# charger.net
KiCad netlist of a schematic drawn in Altium Designer
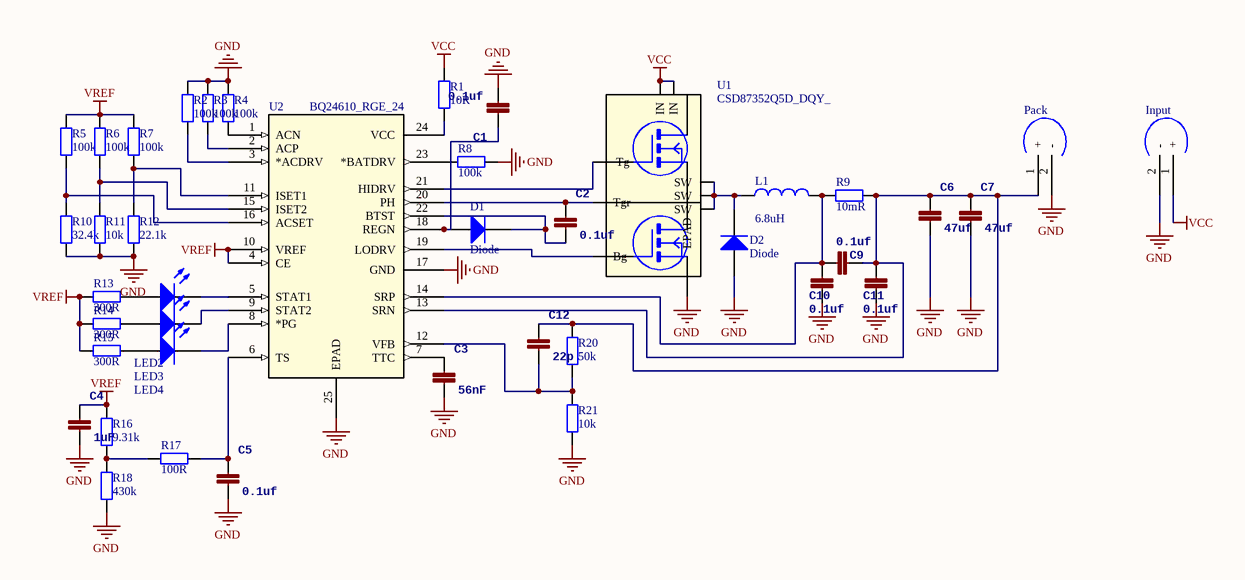
[diagram p0: charger.SchDoc]

(export (version "E")
  (design (tool "Eeschema 10.0.6"))
  (components
    (comp (ref "C1")
      (value "0.1uf")
      (footprint "0603")
      (description "电容")
      (fields (field (name "PARTNO") "CC0402ZRY5V7BB104"))
      (libsource (lib "") (part "CAP0402-CAP_2"))
    )
    (comp (ref "C2")
      (value "0.1uf")
      (footprint "0603")
      (description "电容")
      (fields (field (name "PARTNO") "CC0402ZRY5V7BB104"))
      (libsource (lib "") (part "CAP0402-CAP_1"))
    )
    (comp (ref "C3")
      (value "56nF")
      (footprint "0603")
      (description "电容")
      (fields (field (name "PARTNO") "CC0402ZRY5V7BB104"))
      (libsource (lib "") (part "CAP0402-CAP_1"))
    )
    (comp (ref "C4")
      (value "1uF")
      (footprint "0603")
      (description "电容")
      (fields (field (name "PARTNO") "CC0402ZRY5V7BB104"))
      (libsource (lib "") (part "CAP0402-CAP_1"))
    )
    (comp (ref "C5")
      (value "0.1uf")
      (footprint "0603")
      (description "电容")
      (fields (field (name "PARTNO") "CC0402ZRY5V7BB104"))
      (libsource (lib "") (part "CAP0402-CAP_1"))
    )
    (comp (ref "C6")
      (value "47uf")
      (footprint "1210")
      (description "电容")
      (fields (field (name "PARTNO") "CC0402ZRY5V7BB104"))
      (libsource (lib "") (part "CAP0402-CAP_1"))
    )
    (comp (ref "C7")
      (value "47uf")
      (footprint "1210")
      (description "电容")
      (fields (field (name "PARTNO") "CC0402ZRY5V7BB104"))
      (libsource (lib "") (part "CAP0402-CAP_1"))
    )
    (comp (ref "C9")
      (value "0.1uf")
      (footprint "0603")
      (description "电容")
      (fields (field (name "PARTNO") "CC0402ZRY5V7BB104"))
      (libsource (lib "mcu_board") (part "CAP0402-CAP"))
    )
    (comp (ref "C10")
      (value "0.1uf")
      (footprint "0603")
      (description "电容")
      (fields (field (name "PARTNO") "CC0402ZRY5V7BB104"))
      (libsource (lib "") (part "CAP0402-CAP_2"))
    )
    (comp (ref "C11")
      (value "0.1uf")
      (footprint "0603")
      (description "电容")
      (fields (field (name "PARTNO") "CC0402ZRY5V7BB104"))
      (libsource (lib "") (part "CAP0402-CAP_1"))
    )
    (comp (ref "C12")
      (value "22p")
      (footprint "0603")
      (description "电容")
      (fields (field (name "PARTNO") "CC0402ZRY5V7BB104"))
      (libsource (lib "") (part "CAP0402-CAP_1"))
    )
    (comp (ref "D1")
      (value "Diode")
      (footprint "0805")
      (description "Default Diode")
      (fields (field (name "PUBLISHER") "Altium Limited"))
      (libsource (lib "Miscellaneous Devices") (part "Diode"))
    )
    (comp (ref "D2")
      (value "Diode")
      (footprint "SMC")
      (description "Default Diode")
      (fields (field (name "PUBLISHER") "Altium Limited"))
      (libsource (lib "Miscellaneous Devices") (part "Diode"))
    )
    (comp (ref "Input")
      (value "Battery_AWG12")
      (footprint "Battery_AWG12")
      (libsource (lib "sch") (part "Battery_AWG12"))
    )
    (comp (ref "L1")
      (value "6.8uH")
      (footprint "GDRH127")
      (description "Inductor")
      (fields (field (name "PUBLISHER") "Altium Limited"))
      (libsource (lib "Miscellaneous Devices") (part "Inductor"))
    )
    (comp (ref "LED2")
      (value "LED0")
      (footprint "0603")
      (description "Typical INFRARED GaAs LED")
      (fields (field (name "PUBLISHER") "Altium Limited"))
      (libsource (lib "Miscellaneous Devices") (part "LED0"))
    )
    (comp (ref "LED3")
      (value "LED0")
      (footprint "0603")
      (description "Typical INFRARED GaAs LED")
      (fields (field (name "PUBLISHER") "Altium Limited"))
      (libsource (lib "Miscellaneous Devices") (part "LED0"))
    )
    (comp (ref "LED4")
      (value "LED0")
      (footprint "0603")
      (description "Typical INFRARED GaAs LED")
      (fields (field (name "PUBLISHER") "Altium Limited"))
      (libsource (lib "Miscellaneous Devices") (part "LED0"))
    )
    (comp (ref "Pack")
      (value "Battery_AWG12")
      (footprint "Battery_AWG12")
      (libsource (lib "") (part "Battery_AWG12_1"))
    )
    (comp (ref "R1")
      (value "10R")
      (footprint "0603")
      (description "电阻")
      (fields (field (name "PUBLISHER") "Altium Limited"))
      (libsource (lib "") (part "Res2_2"))
    )
    (comp (ref "R2")
      (value "100k")
      (footprint "0603")
      (description "电阻")
      (fields (field (name "PUBLISHER") "Altium Limited"))
      (libsource (lib "") (part "Res2_2"))
    )
    (comp (ref "R3")
      (value "100k")
      (footprint "0603")
      (description "电阻")
      (fields (field (name "PUBLISHER") "Altium Limited"))
      (libsource (lib "") (part "Res2_2"))
    )
    (comp (ref "R4")
      (value "100k")
      (footprint "0603")
      (description "电阻")
      (fields (field (name "PUBLISHER") "Altium Limited"))
      (libsource (lib "mcu_board") (part "Res2"))
    )
    (comp (ref "R5")
      (value "100k")
      (footprint "0603")
      (description "电阻")
      (fields (field (name "PUBLISHER") "Altium Limited"))
      (libsource (lib "") (part "Res2_2"))
    )
    (comp (ref "R6")
      (value "100k")
      (footprint "0603")
      (description "电阻")
      (fields (field (name "PUBLISHER") "Altium Limited"))
      (libsource (lib "") (part "Res2_2"))
    )
    (comp (ref "R7")
      (value "100k")
      (footprint "0603")
      (description "电阻")
      (fields (field (name "PUBLISHER") "Altium Limited"))
      (libsource (lib "") (part "Res2_2"))
    )
    (comp (ref "R8")
      (value "100k")
      (footprint "0603")
      (description "电阻")
      (fields (field (name "PUBLISHER") "Altium Limited"))
      (libsource (lib "") (part "Res2_1"))
    )
    (comp (ref "R9")
      (value "10mR")
      (footprint "2512")
      (description "电阻")
      (fields (field (name "PUBLISHER") "Altium Limited"))
      (libsource (lib "") (part "Res2_1"))
    )
    (comp (ref "R10")
      (value "32.4k")
      (footprint "0603")
      (description "电阻")
      (fields (field (name "PUBLISHER") "Altium Limited"))
      (libsource (lib "") (part "Res2_2"))
    )
    (comp (ref "R11")
      (value "10k")
      (footprint "0603")
      (description "电阻")
      (fields (field (name "PUBLISHER") "Altium Limited"))
      (libsource (lib "") (part "Res2_2"))
    )
    (comp (ref "R12")
      (value "22.1k")
      (footprint "0603")
      (description "电阻")
      (fields (field (name "PUBLISHER") "Altium Limited"))
      (libsource (lib "") (part "Res2_2"))
    )
    (comp (ref "R13")
      (value "300R")
      (footprint "0603")
      (description "电阻")
      (fields (field (name "PUBLISHER") "Altium Limited"))
      (libsource (lib "") (part "Res2_1"))
    )
    (comp (ref "R14")
      (value "300R")
      (footprint "0603")
      (description "电阻")
      (fields (field (name "PUBLISHER") "Altium Limited"))
      (libsource (lib "") (part "Res2_1"))
    )
    (comp (ref "R15")
      (value "300R")
      (footprint "0603")
      (description "电阻")
      (fields (field (name "PUBLISHER") "Altium Limited"))
      (libsource (lib "") (part "Res2_1"))
    )
    (comp (ref "R16")
      (value "9.31k")
      (footprint "0603")
      (description "电阻")
      (fields (field (name "PUBLISHER") "Altium Limited"))
      (libsource (lib "mcu_board") (part "Res2"))
    )
    (comp (ref "R17")
      (value "100R")
      (footprint "0603")
      (description "电阻")
      (fields (field (name "PUBLISHER") "Altium Limited"))
      (libsource (lib "") (part "Res2_1"))
    )
    (comp (ref "R18")
      (value "430k")
      (footprint "0603")
      (description "电阻")
      (fields (field (name "PUBLISHER") "Altium Limited"))
      (libsource (lib "mcu_board") (part "Res2"))
    )
    (comp (ref "R20")
      (value "50k")
      (footprint "0603")
      (description "电阻")
      (fields (field (name "PUBLISHER") "Altium Limited"))
      (libsource (lib "") (part "Res2_2"))
    )
    (comp (ref "R21")
      (value "10k")
      (footprint "0603")
      (description "电阻")
      (fields (field (name "PUBLISHER") "Altium Limited"))
      (libsource (lib "") (part "Res2_2"))
    )
    (comp (ref "U1")
      (value "CSD87352Q5D_DQY_")
      (footprint "CSD87352Q5D")
      (description "Imported")
      (fields
        (field (name "MANUFACTURER") "Texas Instruments")
        (field (name "GENERIC_PART_NUMBER") "CSD87352Q5D")
      )
      (libsource (lib "CSD87352Q5D") (part "CSD87352Q5D_DQY_"))
    )
    (comp (ref "U2")
      (value "BQ24610_RGE_24")
      (footprint "BQ24610")
      (description "Imported")
      (fields
        (field (name "MANUFACTURER") "Texas Instruments")
        (field (name "GENERIC_PART_NUMBER") "BQ24610")
      )
      (libsource (lib "sch") (part "BQ24610_RGE_24"))
    )
  )
  (nets
    (net (code "1") (name "GND") (class "Default")
      (node (ref "C1") (pin "1") (pinfunction "1_1") (pintype "passive"))
      (node (ref "C10") (pin "2") (pinfunction "2_2") (pintype "passive"))
      (node (ref "C11") (pin "1") (pinfunction "1_1") (pintype "passive"))
      (node (ref "C3") (pin "1") (pinfunction "1_1") (pintype "passive"))
      (node (ref "C4") (pin "1") (pinfunction "1_1") (pintype "passive"))
      (node (ref "C5") (pin "1") (pinfunction "1_1") (pintype "passive"))
      (node (ref "C6") (pin "1") (pinfunction "1_1") (pintype "passive"))
      (node (ref "C7") (pin "1") (pinfunction "1_1") (pintype "passive"))
      (node (ref "D2") (pin "1") (pinfunction "A_1") (pintype "passive"))
      (node (ref "Input") (pin "2") (pinfunction "-_2") (pintype "passive"))
      (node (ref "Pack") (pin "2") (pinfunction "-_2") (pintype "passive"))
      (node (ref "R10") (pin "2") (pinfunction "2_2") (pintype "passive"))
      (node (ref "R11") (pin "2") (pinfunction "2_2") (pintype "passive"))
      (node (ref "R12") (pin "2") (pinfunction "2_2") (pintype "passive"))
      (node (ref "R18") (pin "1") (pinfunction "1_1") (pintype "passive"))
      (node (ref "R2") (pin "1") (pinfunction "1_1") (pintype "passive"))
      (node (ref "R21") (pin "2") (pinfunction "2_2") (pintype "passive"))
      (node (ref "R3") (pin "1") (pinfunction "1_1") (pintype "passive"))
      (node (ref "R4") (pin "2") (pinfunction "2_2") (pintype "passive"))
      (node (ref "R8") (pin "2") (pinfunction "2_2") (pintype "passive"))
      (node (ref "U1") (pin "9") (pinfunction "EPAD_9") (pintype "power_in"))
      (node (ref "U2") (pin "17") (pinfunction "GND_17") (pintype "power_in"))
      (node (ref "U2") (pin "25") (pinfunction "EPAD_25") (pintype "power_in"))
    )
    (net (code "2") (name "Net-(D1-A)") (class "Default")
      (node (ref "C1") (pin "2") (pinfunction "2_2") (pintype "passive"))
      (node (ref "D1") (pin "1") (pinfunction "A_1") (pintype "passive"))
      (node (ref "U2") (pin "18") (pinfunction "REGN_18") (pintype "output"))
    )
    (net (code "3") (name "Net-(D1-K)") (class "Default")
      (node (ref "C2") (pin "1") (pinfunction "1_1") (pintype "passive"))
      (node (ref "D1") (pin "2") (pinfunction "K_2") (pintype "passive"))
      (node (ref "U2") (pin "22") (pinfunction "BTST_22") (pintype "output"))
    )
    (net (code "4") (name "Net-(D2-K)") (class "Default")
      (node (ref "D2") (pin "2") (pinfunction "K_2") (pintype "passive"))
      (node (ref "L1") (pin "1") (pinfunction "1_1") (pintype "passive"))
      (node (ref "U1") (pin "6") (pinfunction "SW_6") (pintype "passive"))
      (node (ref "U1") (pin "7") (pinfunction "SW_7") (pintype "passive"))
      (node (ref "U1") (pin "8") (pinfunction "SW_8") (pintype "passive"))
    )
    (net (code "5") (name "Net-(LED2-A)") (class "Default")
      (node (ref "LED2") (pin "1") (pinfunction "A_1") (pintype "passive"))
      (node (ref "R13") (pin "2") (pinfunction "2_2") (pintype "passive"))
    )
    (net (code "6") (name "Net-(LED2-K)") (class "Default")
      (node (ref "LED2") (pin "2") (pinfunction "K_2") (pintype "passive"))
      (node (ref "U2") (pin "5") (pinfunction "STAT1_5") (pintype "input"))
    )
    (net (code "7") (name "Net-(LED3-A)") (class "Default")
      (node (ref "LED3") (pin "1") (pinfunction "A_1") (pintype "passive"))
      (node (ref "R14") (pin "2") (pinfunction "2_2") (pintype "passive"))
    )
    (net (code "8") (name "Net-(LED3-K)") (class "Default")
      (node (ref "LED3") (pin "2") (pinfunction "K_2") (pintype "passive"))
      (node (ref "U2") (pin "9") (pinfunction "STAT2_9") (pintype "input"))
    )
    (net (code "9") (name "Net-(LED4-A)") (class "Default")
      (node (ref "LED4") (pin "1") (pinfunction "A_1") (pintype "passive"))
      (node (ref "R15") (pin "2") (pinfunction "2_2") (pintype "passive"))
    )
    (net (code "10") (name "Net-(LED4-K)") (class "Default")
      (node (ref "LED4") (pin "2") (pinfunction "K_2") (pintype "passive"))
      (node (ref "U2") (pin "8") (pinfunction "*PG_8") (pintype "input"))
    )
    (net (code "11") (name "Net-(Pack-+)") (class "Default")
      (node (ref "C11") (pin "2") (pinfunction "2_2") (pintype "passive"))
      (node (ref "C12") (pin "2") (pinfunction "2_2") (pintype "passive"))
      (node (ref "C6") (pin "2") (pinfunction "2_2") (pintype "passive"))
      (node (ref "C7") (pin "2") (pinfunction "2_2") (pintype "passive"))
      (node (ref "C9") (pin "1") (pinfunction "1_1") (pintype "passive"))
      (node (ref "Pack") (pin "1") (pinfunction "+_1") (pintype "passive"))
      (node (ref "R20") (pin "1") (pinfunction "1_1") (pintype "passive"))
      (node (ref "R9") (pin "2") (pinfunction "2_2") (pintype "passive"))
      (node (ref "U2") (pin "13") (pinfunction "SRN_13") (pintype "output"))
    )
    (net (code "12") (name "Net-(R16-Pad1)") (class "Default")
      (node (ref "R16") (pin "1") (pinfunction "1_1") (pintype "passive"))
      (node (ref "R17") (pin "1") (pinfunction "1_1") (pintype "passive"))
      (node (ref "R18") (pin "2") (pinfunction "2_2") (pintype "passive"))
    )
    (net (code "13") (name "Net-(U1-Bg)") (class "Default")
      (node (ref "U1") (pin "5") (pinfunction "Bg_5") (pintype "passive"))
      (node (ref "U2") (pin "19") (pinfunction "LODRV_19") (pintype "output"))
    )
    (net (code "14") (name "Net-(U1-Tg)") (class "Default")
      (node (ref "U1") (pin "3") (pinfunction "Tg_3") (pintype "passive"))
      (node (ref "U2") (pin "21") (pinfunction "HIDRV_21") (pintype "output"))
    )
    (net (code "15") (name "Net-(U1-Tgr)") (class "Default")
      (node (ref "C2") (pin "2") (pinfunction "2_2") (pintype "passive"))
      (node (ref "U1") (pin "4") (pinfunction "Tgr_4") (pintype "passive"))
      (node (ref "U2") (pin "20") (pinfunction "PH_20") (pintype "output"))
    )
    (net (code "16") (name "Net-(U2-*ACDRV)") (class "Default")
      (node (ref "R2") (pin "2") (pinfunction "2_2") (pintype "passive"))
      (node (ref "U2") (pin "3") (pinfunction "*ACDRV_3") (pintype "input"))
    )
    (net (code "17") (name "Net-(U2-*BATDRV)") (class "Default")
      (node (ref "R8") (pin "1") (pinfunction "1_1") (pintype "passive"))
      (node (ref "U2") (pin "23") (pinfunction "*BATDRV_23") (pintype "output"))
    )
    (net (code "18") (name "Net-(U2-ACN)") (class "Default")
      (node (ref "R4") (pin "1") (pinfunction "1_1") (pintype "passive"))
      (node (ref "U2") (pin "1") (pinfunction "ACN_1") (pintype "input"))
    )
    (net (code "19") (name "Net-(U2-ACP)") (class "Default")
      (node (ref "R3") (pin "2") (pinfunction "2_2") (pintype "passive"))
      (node (ref "U2") (pin "2") (pinfunction "ACP_2") (pintype "input"))
    )
    (net (code "20") (name "Net-(U2-ACSET)") (class "Default")
      (node (ref "R10") (pin "1") (pinfunction "1_1") (pintype "passive"))
      (node (ref "R5") (pin "2") (pinfunction "2_2") (pintype "passive"))
      (node (ref "U2") (pin "16") (pinfunction "ACSET_16") (pintype "input"))
    )
    (net (code "21") (name "Net-(U2-ISET1)") (class "Default")
      (node (ref "R12") (pin "1") (pinfunction "1_1") (pintype "passive"))
      (node (ref "R7") (pin "2") (pinfunction "2_2") (pintype "passive"))
      (node (ref "U2") (pin "11") (pinfunction "ISET1_11") (pintype "input"))
    )
    (net (code "22") (name "Net-(U2-ISET2)") (class "Default")
      (node (ref "R11") (pin "1") (pinfunction "1_1") (pintype "passive"))
      (node (ref "R6") (pin "2") (pinfunction "2_2") (pintype "passive"))
      (node (ref "U2") (pin "15") (pinfunction "ISET2_15") (pintype "input"))
    )
    (net (code "23") (name "Net-(U2-SRP)") (class "Default")
      (node (ref "C10") (pin "1") (pinfunction "1_1") (pintype "passive"))
      (node (ref "C9") (pin "2") (pinfunction "2_2") (pintype "passive"))
      (node (ref "L1") (pin "2") (pinfunction "2_2") (pintype "passive"))
      (node (ref "R9") (pin "1") (pinfunction "1_1") (pintype "passive"))
      (node (ref "U2") (pin "14") (pinfunction "SRP_14") (pintype "output"))
    )
    (net (code "24") (name "Net-(U2-TS)") (class "Default")
      (node (ref "C5") (pin "2") (pinfunction "2_2") (pintype "passive"))
      (node (ref "R17") (pin "2") (pinfunction "2_2") (pintype "passive"))
      (node (ref "U2") (pin "6") (pinfunction "TS_6") (pintype "input"))
    )
    (net (code "25") (name "Net-(U2-TTC)") (class "Default")
      (node (ref "C3") (pin "2") (pinfunction "2_2") (pintype "passive"))
      (node (ref "U2") (pin "7") (pinfunction "TTC_7") (pintype "output"))
    )
    (net (code "26") (name "Net-(U2-VCC)") (class "Default")
      (node (ref "R1") (pin "2") (pinfunction "2_2") (pintype "passive"))
      (node (ref "U2") (pin "24") (pinfunction "VCC_24") (pintype "power_in"))
    )
    (net (code "27") (name "Net-(U2-VFB)") (class "Default")
      (node (ref "C12") (pin "1") (pinfunction "1_1") (pintype "passive"))
      (node (ref "R20") (pin "2") (pinfunction "2_2") (pintype "passive"))
      (node (ref "R21") (pin "1") (pinfunction "1_1") (pintype "passive"))
      (node (ref "U2") (pin "12") (pinfunction "VFB_12") (pintype "output"))
    )
    (net (code "28") (name "VCC") (class "Default")
      (node (ref "Input") (pin "1") (pinfunction "+_1") (pintype "passive"))
      (node (ref "R1") (pin "1") (pinfunction "1_1") (pintype "passive"))
      (node (ref "U1") (pin "1") (pinfunction "IN_1") (pintype "passive"))
      (node (ref "U1") (pin "2") (pinfunction "IN_2") (pintype "passive"))
    )
    (net (code "29") (name "VREF") (class "Default")
      (node (ref "C4") (pin "2") (pinfunction "2_2") (pintype "passive"))
      (node (ref "R13") (pin "1") (pinfunction "1_1") (pintype "passive"))
      (node (ref "R14") (pin "1") (pinfunction "1_1") (pintype "passive"))
      (node (ref "R15") (pin "1") (pinfunction "1_1") (pintype "passive"))
      (node (ref "R16") (pin "2") (pinfunction "2_2") (pintype "passive"))
      (node (ref "R5") (pin "1") (pinfunction "1_1") (pintype "passive"))
      (node (ref "R6") (pin "1") (pinfunction "1_1") (pintype "passive"))
      (node (ref "R7") (pin "1") (pinfunction "1_1") (pintype "passive"))
      (node (ref "U2") (pin "10") (pinfunction "VREF_10") (pintype "input"))
      (node (ref "U2") (pin "4") (pinfunction "CE_4") (pintype "input"))
    )
  )
)
